# OSSIEPSNew.net
KiCad netlist of a schematic drawn in EAGLE
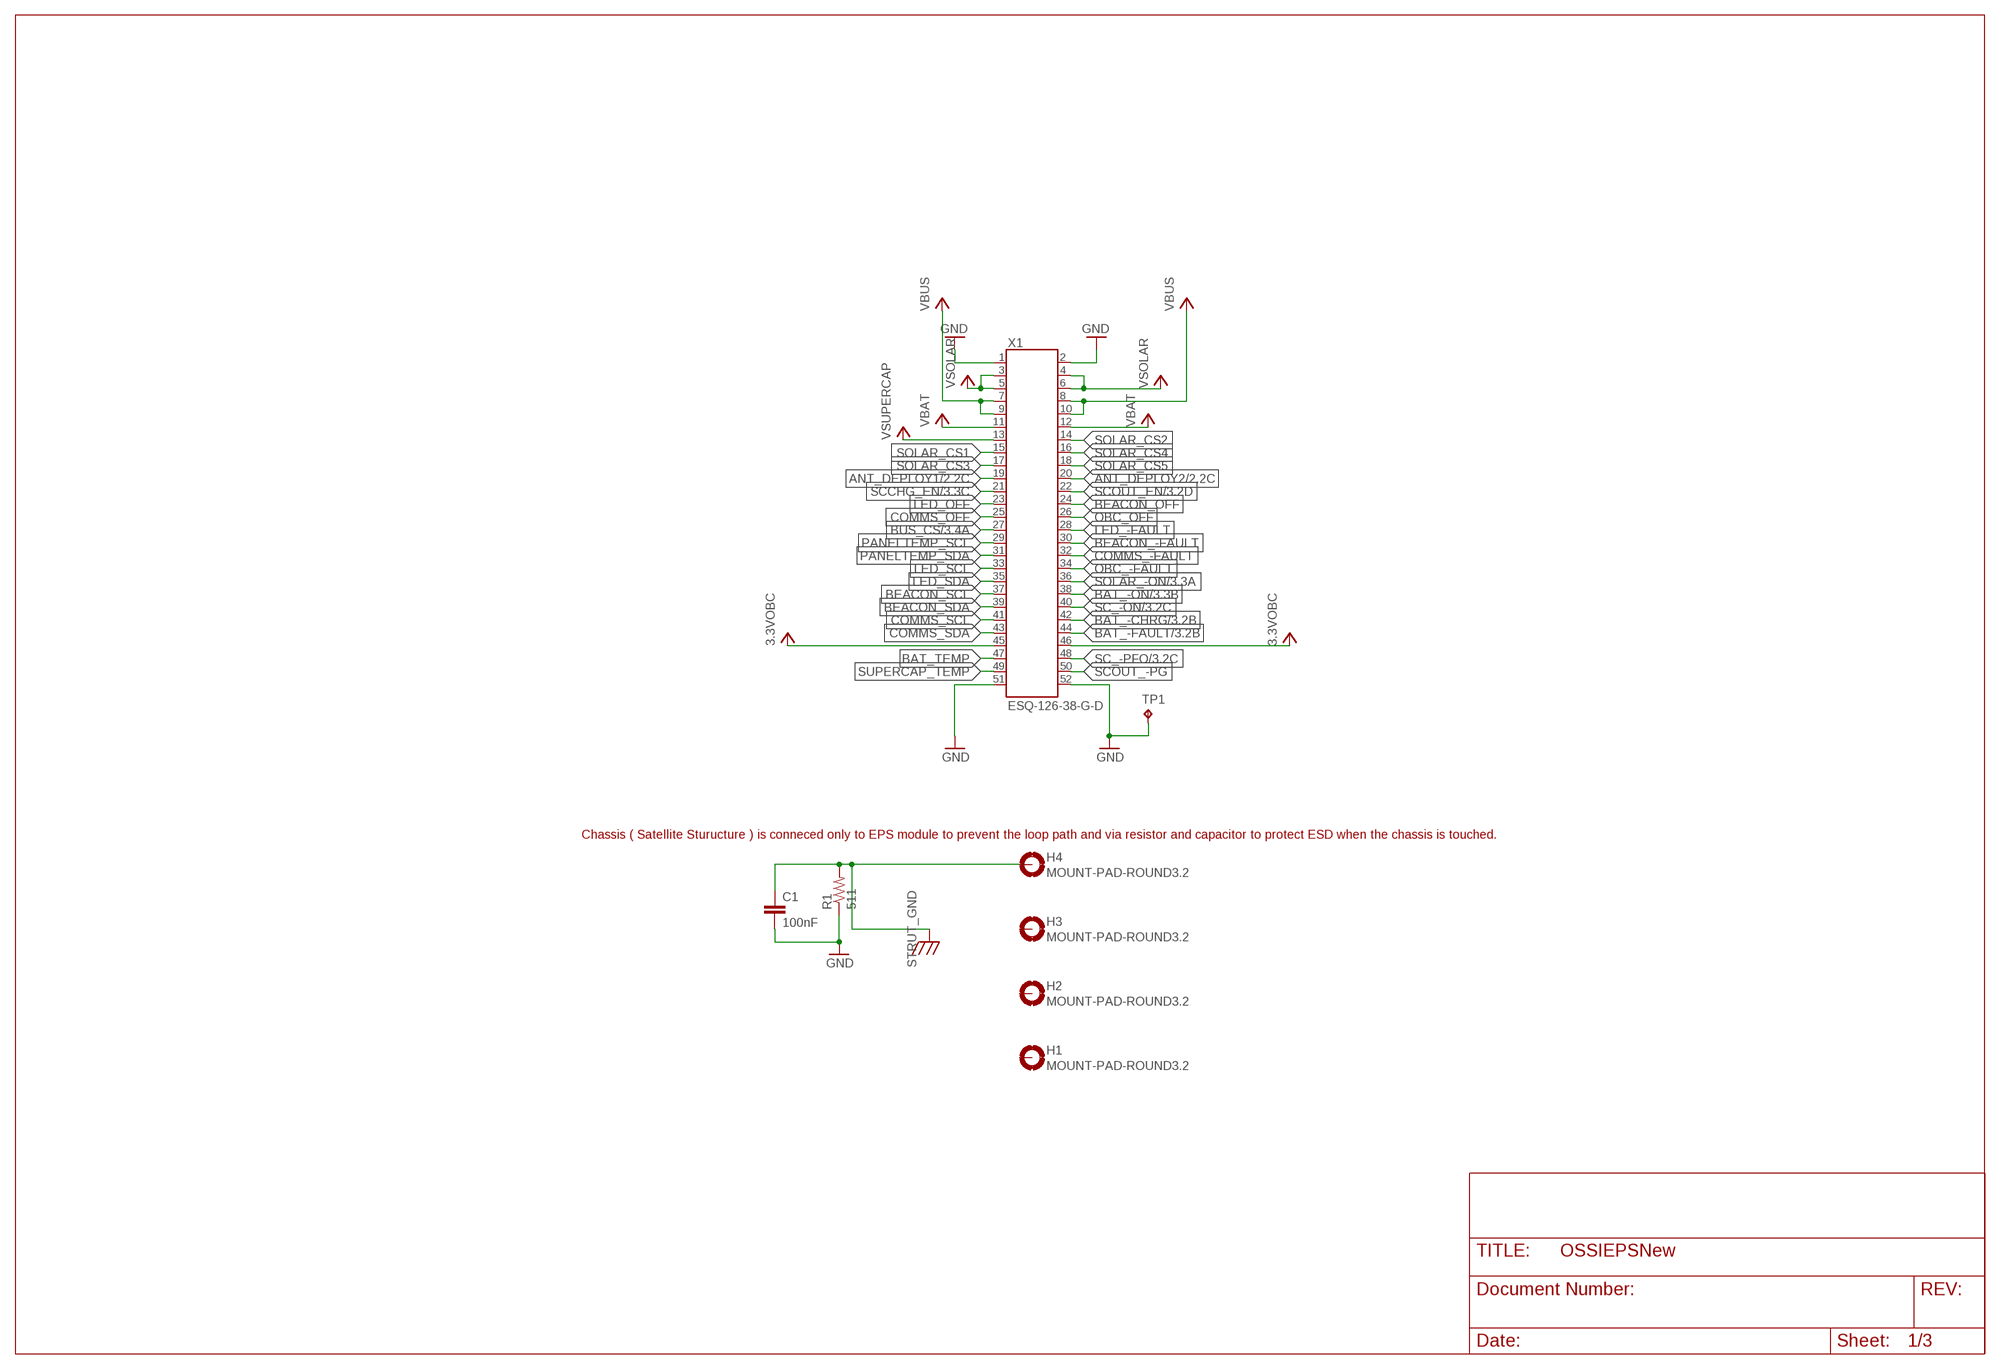
[diagram p0: schematic, sheet 1]
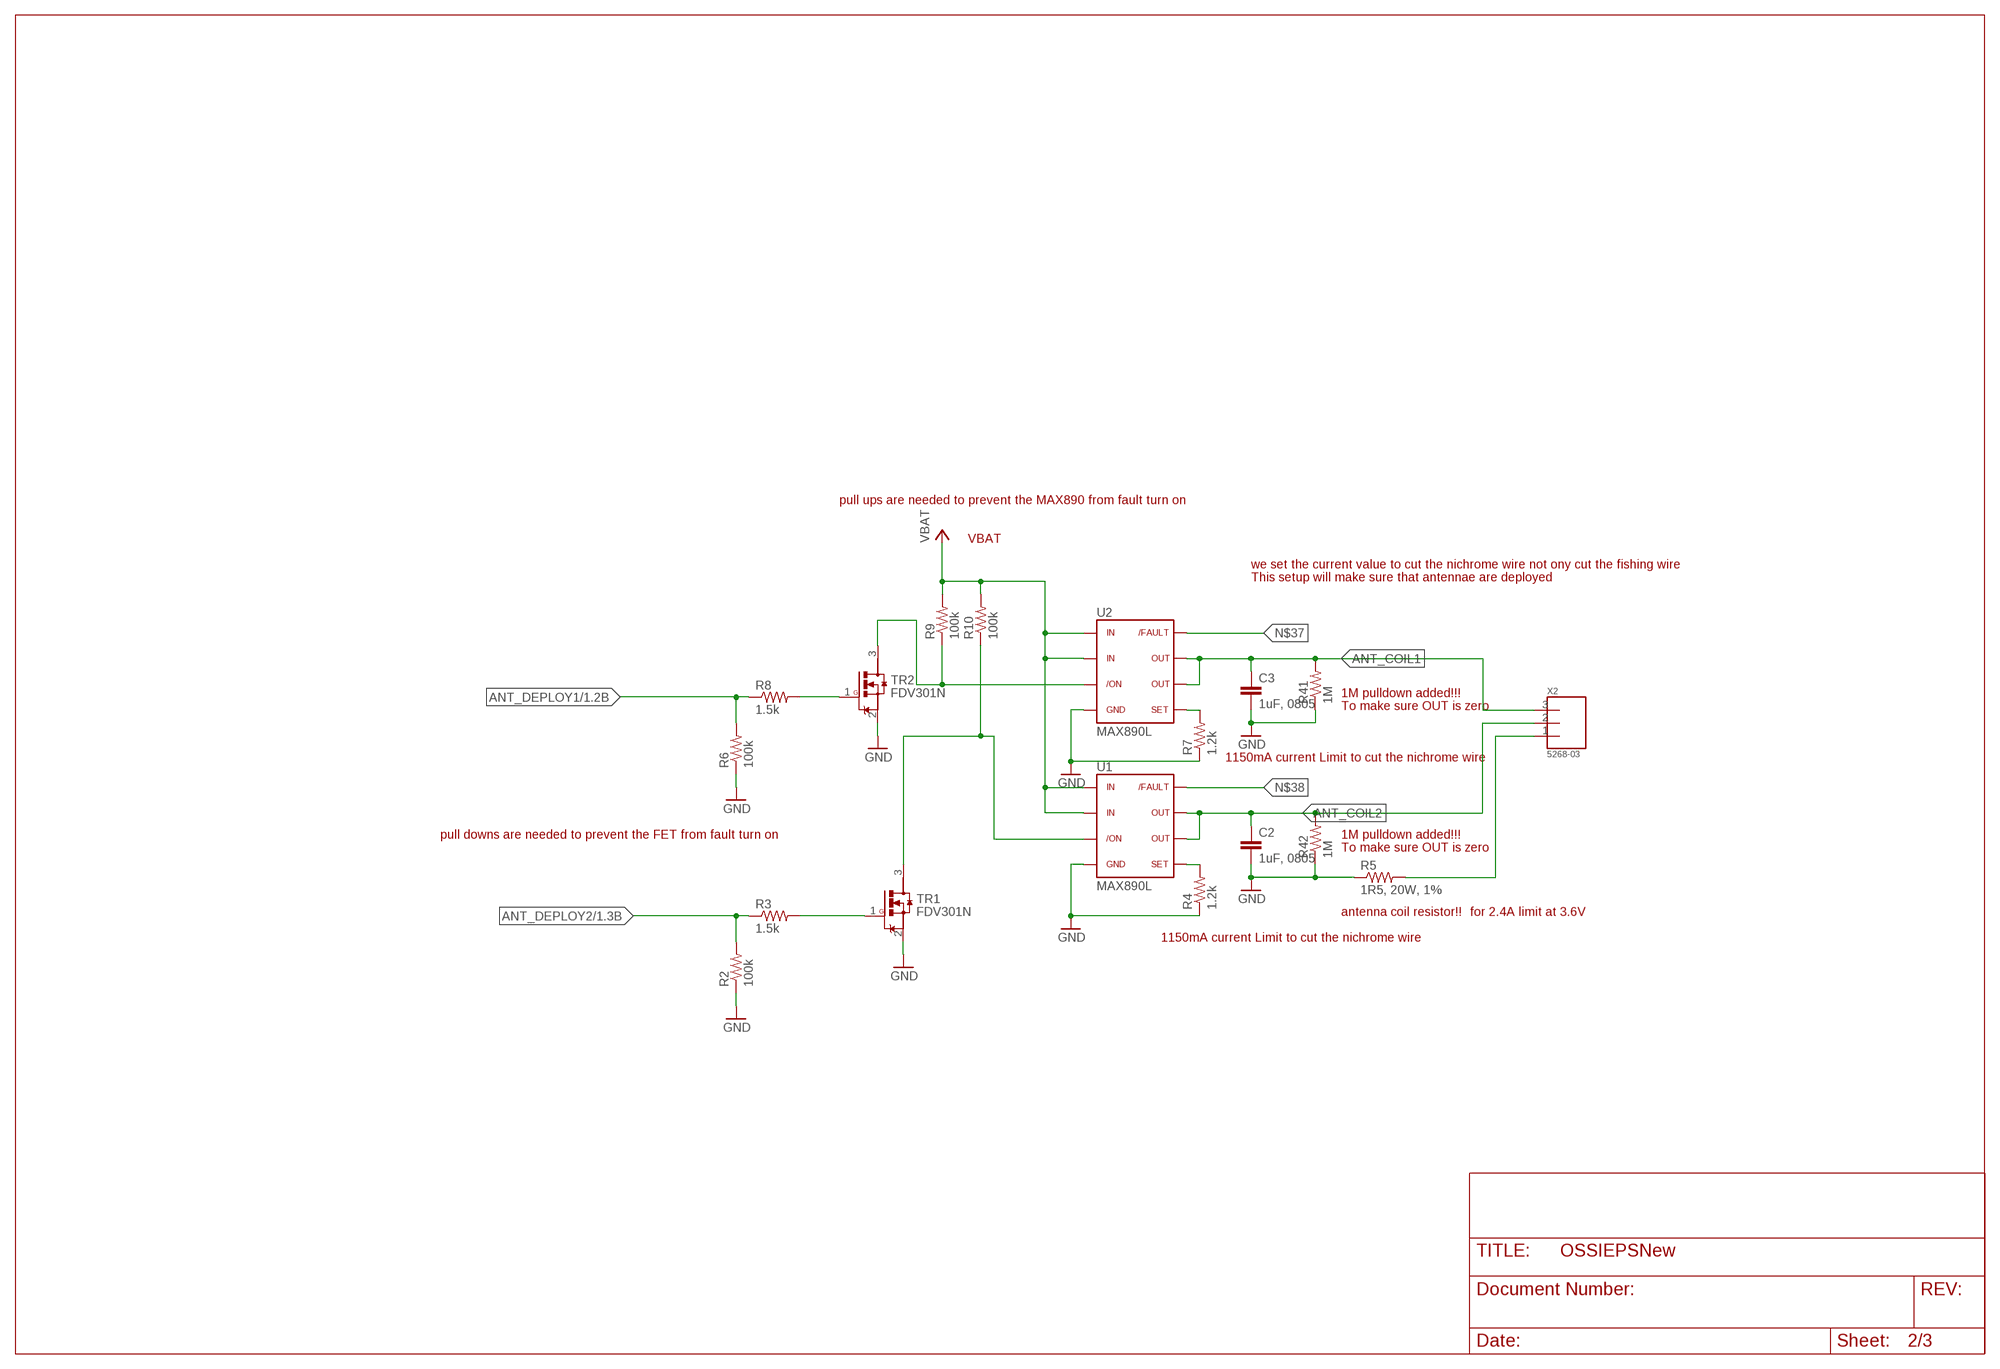
[diagram p1: schematic, sheet 2]
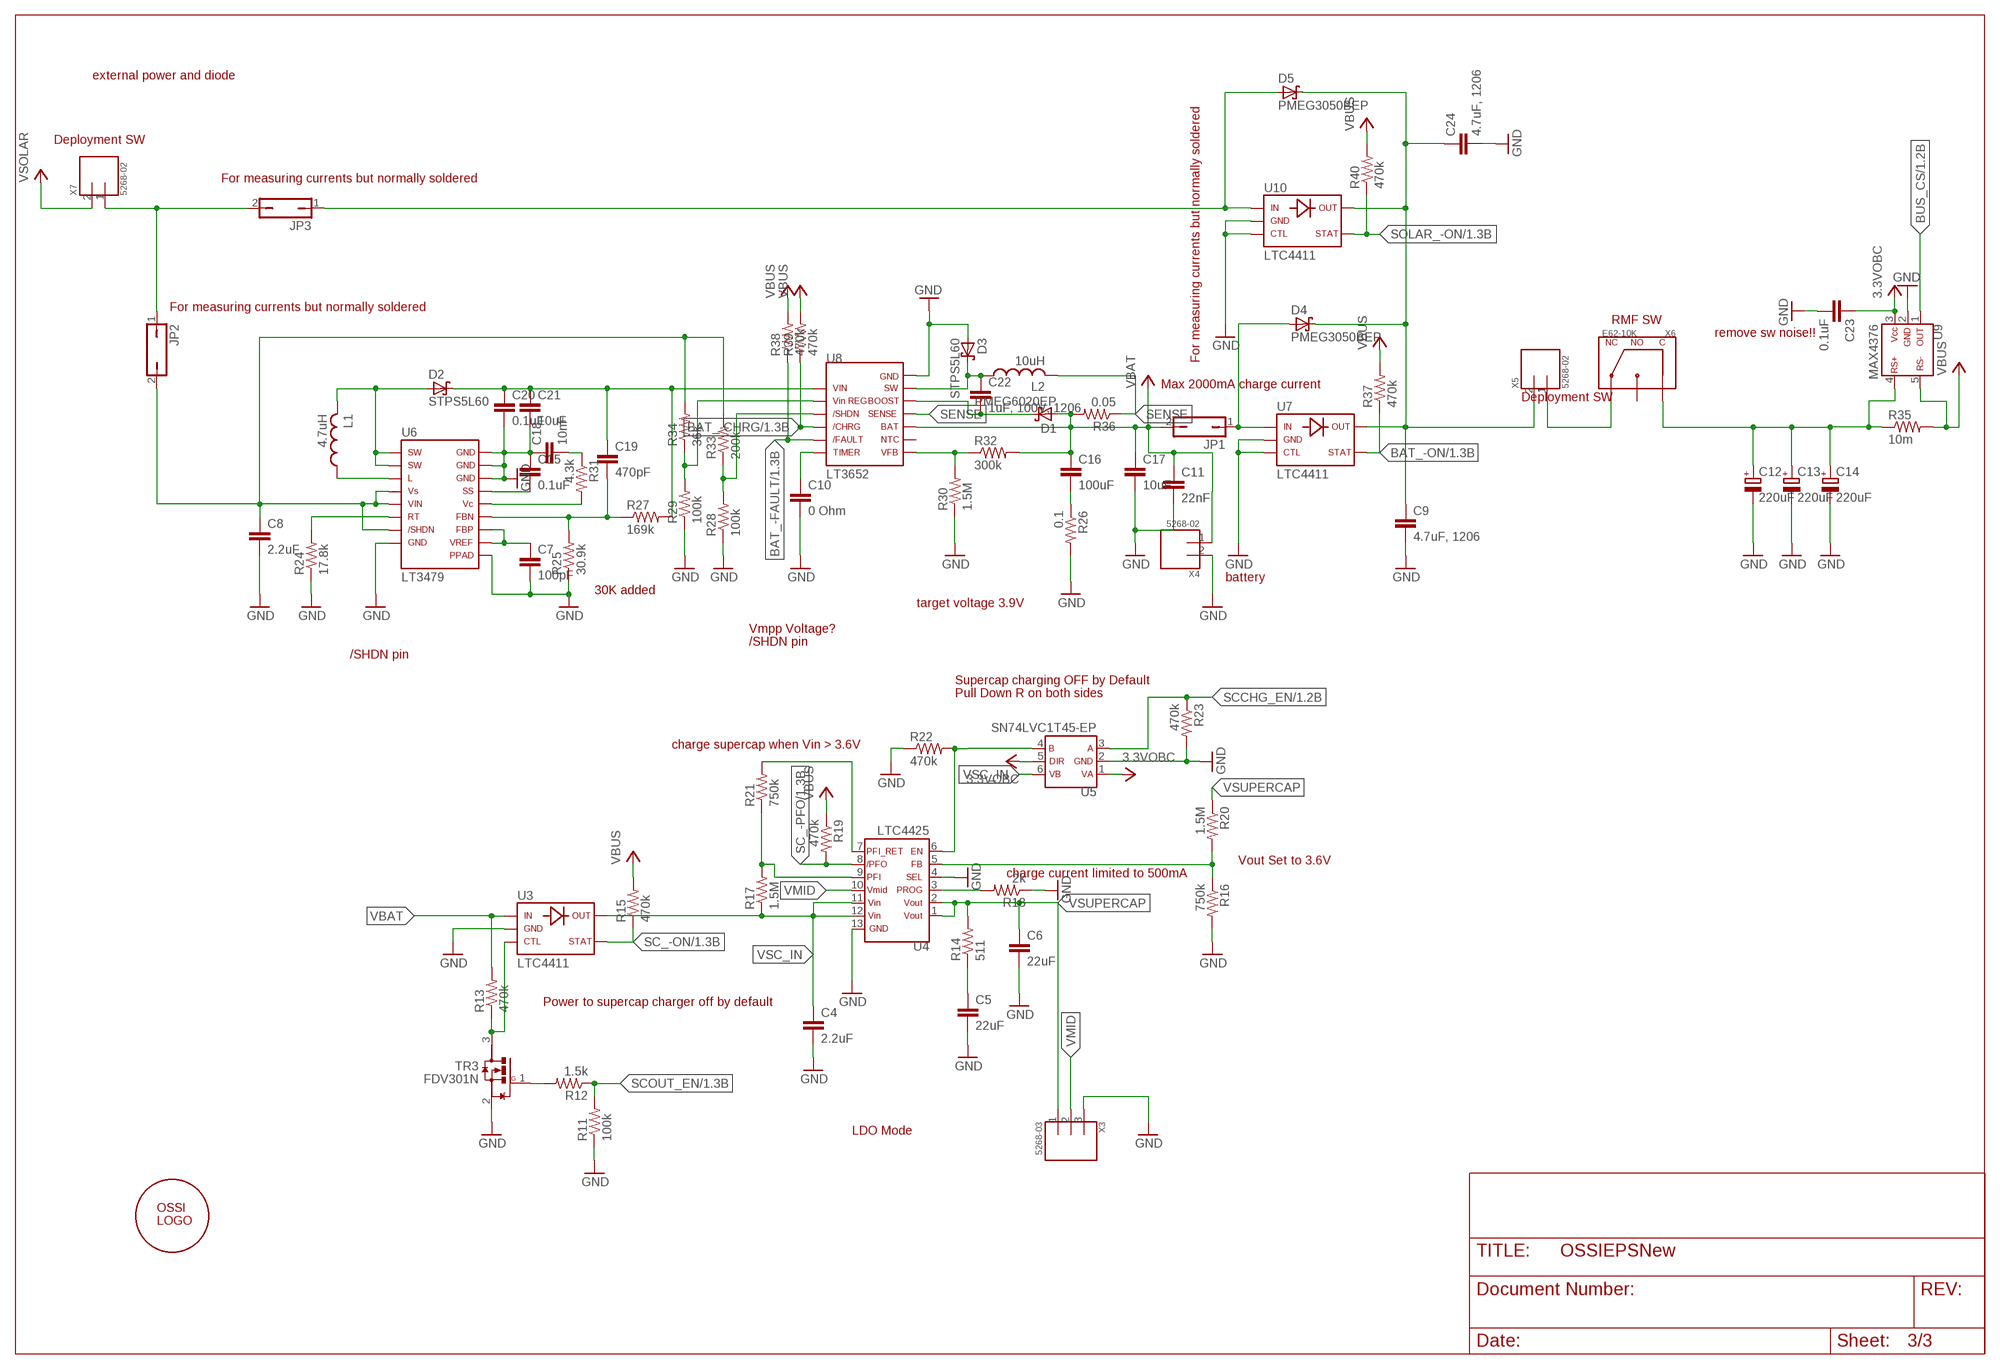
[diagram p2: schematic, sheet 3]

(export (version "E")
  (design (tool "Eeschema 10.0.6"))
  (components
    (comp (ref "C2")
      (value "1uF, 0805")
      (footprint "eagle-import:C0805(2012)")
      (libsource (lib "eagle-import") (part "C0805(2012)"))
    )
    (comp (ref "C3")
      (value "1uF, 0805")
      (footprint "eagle-import:C0805(2012)")
      (libsource (lib "eagle-import") (part "C0805(2012)"))
    )
    (comp (ref "R2")
      (value "100k")
      (footprint "eagle-import:R0603(1608)")
      (libsource (lib "eagle-import") (part "R0603(1608)"))
    )
    (comp (ref "R3")
      (value "1.5k")
      (footprint "eagle-import:R0603(1608)")
      (libsource (lib "eagle-import") (part "R0603(1608)"))
    )
    (comp (ref "R4")
      (value "1.2k")
      (footprint "eagle-import:R0603(1608)")
      (libsource (lib "eagle-import") (part "R0603(1608)"))
    )
    (comp (ref "R5")
      (value "1R5, 20W, 1%")
      (footprint "eagle-import:PWR263S-20")
      (libsource (lib "eagle-import") (part "RPWR263S"))
    )
    (comp (ref "R6")
      (value "100k")
      (footprint "eagle-import:R0603(1608)")
      (libsource (lib "eagle-import") (part "R0603(1608)"))
    )
    (comp (ref "R7")
      (value "1.2k")
      (footprint "eagle-import:R0603(1608)")
      (libsource (lib "eagle-import") (part "R0603(1608)"))
    )
    (comp (ref "R8")
      (value "1.5k")
      (footprint "eagle-import:R0603(1608)")
      (libsource (lib "eagle-import") (part "R0603(1608)"))
    )
    (comp (ref "R9")
      (value "100k")
      (footprint "eagle-import:R0603(1608)")
      (libsource (lib "eagle-import") (part "R0603(1608)"))
    )
    (comp (ref "R10")
      (value "100k")
      (footprint "eagle-import:R0603(1608)")
      (libsource (lib "eagle-import") (part "R0603(1608)"))
    )
    (comp (ref "R41")
      (value "1M")
      (footprint "eagle-import:R0603(1608)")
      (libsource (lib "eagle-import") (part "R0603(1608)"))
    )
    (comp (ref "R42")
      (value "1M")
      (footprint "eagle-import:R0603(1608)")
      (libsource (lib "eagle-import") (part "R0603(1608)"))
    )
    (comp (ref "TR1")
      (value "FDV301N")
      (footprint "eagle-import:SOT23")
      (libsource (lib "eagle-import") (part "FDV301N"))
    )
    (comp (ref "TR2")
      (value "FDV301N")
      (footprint "eagle-import:SOT23")
      (libsource (lib "eagle-import") (part "FDV301N"))
    )
    (comp (ref "U1")
      (value "MAX890L")
      (footprint "eagle-import:SO8")
      (libsource (lib "eagle-import") (part "MAX890L"))
    )
    (comp (ref "U2")
      (value "MAX890L")
      (footprint "eagle-import:SO8")
      (libsource (lib "eagle-import") (part "MAX890L"))
    )
    (comp (ref "X2")
      (value "5268-03")
      (footprint "eagle-import:5268-03")
      (libsource (lib "eagle-import") (part "5268-03"))
    )
    (comp (ref "C1")
      (value "100nF")
      (footprint "eagle-import:C0805(2012)")
      (libsource (lib "eagle-import") (part "C0805(2012)"))
    )
    (comp (ref "H1")
      (value "MOUNT-PAD-ROUND3.2")
      (footprint "eagle-import:3.2-PAD-ROUND")
      (libsource (lib "eagle-import") (part "MOUNT-PAD-ROUND3.2"))
    )
    (comp (ref "H2")
      (value "MOUNT-PAD-ROUND3.2")
      (footprint "eagle-import:3.2-PAD-ROUND")
      (libsource (lib "eagle-import") (part "MOUNT-PAD-ROUND3.2"))
    )
    (comp (ref "H3")
      (value "MOUNT-PAD-ROUND3.2")
      (footprint "eagle-import:3.2-PAD-ROUND")
      (libsource (lib "eagle-import") (part "MOUNT-PAD-ROUND3.2"))
    )
    (comp (ref "H4")
      (value "MOUNT-PAD-ROUND3.2")
      (footprint "eagle-import:3.2-PAD-ROUND")
      (libsource (lib "eagle-import") (part "MOUNT-PAD-ROUND3.2"))
    )
    (comp (ref "R1")
      (value "511")
      (footprint "eagle-import:WSL1206")
      (libsource (lib "eagle-import") (part "RWSL1206"))
    )
    (comp (ref "TP1")
      (value "TP")
      (footprint "eagle-import:TP-13")
      (libsource (lib "eagle-import") (part "TP"))
    )
    (comp (ref "X1")
      (value "ESQ-126-38-G-D")
      (footprint "eagle-import:ESQ-126-XX-X-D")
      (libsource (lib "eagle-import") (part "ESQ-126-38-G-D"))
    )
    (comp (ref "C4")
      (value "2.2uF")
      (footprint "eagle-import:C1206-GCM31")
      (libsource (lib "eagle-import") (part "C1206(3216)-GCM31"))
    )
    (comp (ref "C5")
      (value "22uF")
      (footprint "eagle-import:C1210-GCM32")
      (libsource (lib "eagle-import") (part "C1210(3225)-GCM32"))
    )
    (comp (ref "C6")
      (value "22uF")
      (footprint "eagle-import:C1210-GCM32")
      (libsource (lib "eagle-import") (part "C1210(3225)-GCM32"))
    )
    (comp (ref "C7")
      (value "100pF")
      (footprint "eagle-import:C0603(1608)")
      (libsource (lib "eagle-import") (part "C0603(1608)"))
    )
    (comp (ref "C8")
      (value "2.2uF")
      (footprint "eagle-import:C1206-GCM31")
      (libsource (lib "eagle-import") (part "C1206(3216)-GCM31"))
    )
    (comp (ref "C9")
      (value "4.7uF, 1206")
      (footprint "eagle-import:C1206-GCM31")
      (libsource (lib "eagle-import") (part "C1206(3216)-GCM31"))
    )
    (comp (ref "C10")
      (value "0 Ohm")
      (footprint "eagle-import:C0603(1608)")
      (libsource (lib "eagle-import") (part "C0603(1608)"))
    )
    (comp (ref "C11")
      (value "22nF")
      (footprint "eagle-import:C0603(1608)")
      (libsource (lib "eagle-import") (part "C0603(1608)"))
    )
    (comp (ref "C12")
      (value "220uF")
      (footprint "eagle-import:C2917(7343)-Y")
      (libsource (lib "eagle-import") (part "C-TANTAL-Y"))
    )
    (comp (ref "C13")
      (value "220uF")
      (footprint "eagle-import:C2917(7343)-Y")
      (libsource (lib "eagle-import") (part "C-TANTAL-Y"))
    )
    (comp (ref "C14")
      (value "220uF")
      (footprint "eagle-import:C2917(7343)-Y")
      (libsource (lib "eagle-import") (part "C-TANTAL-Y"))
    )
    (comp (ref "C15")
      (value "0.1uF")
      (footprint "eagle-import:C0603(1608)")
      (libsource (lib "eagle-import") (part "C0603(1608)"))
    )
    (comp (ref "C16")
      (value "100uF")
      (footprint "eagle-import:C1210-TMK325")
      (libsource (lib "eagle-import") (part "C1210(3225)-TMK325"))
    )
    (comp (ref "C17")
      (value "10uF")
      (footprint "eagle-import:C1210-GCM32")
      (libsource (lib "eagle-import") (part "C1210(3225)-GCM32"))
    )
    (comp (ref "C18")
      (value "10nF")
      (footprint "eagle-import:C0603(1608)")
      (libsource (lib "eagle-import") (part "C0603(1608)"))
    )
    (comp (ref "C19")
      (value "470pF")
      (footprint "eagle-import:C0603(1608)")
      (libsource (lib "eagle-import") (part "C0603(1608)"))
    )
    (comp (ref "C20")
      (value "0.1uF")
      (footprint "eagle-import:C0603(1608)")
      (libsource (lib "eagle-import") (part "C0603(1608)"))
    )
    (comp (ref "C21")
      (value "10uF")
      (footprint "eagle-import:C1210-GCM32")
      (libsource (lib "eagle-import") (part "C1210(3225)-GCM32"))
    )
    (comp (ref "C22")
      (value "1uF, 100V, 1206")
      (footprint "eagle-import:C0805(2012)")
      (libsource (lib "eagle-import") (part "C0805(2012)"))
    )
    (comp (ref "C23")
      (value "0.1uF")
      (footprint "eagle-import:C0603(1608)")
      (libsource (lib "eagle-import") (part "C0603(1608)"))
    )
    (comp (ref "C24")
      (value "4.7uF, 1206")
      (footprint "eagle-import:C1206-GCM31")
      (libsource (lib "eagle-import") (part "C1206(3216)-GCM31"))
    )
    (comp (ref "D1")
      (value "PMEG6020EP")
      (footprint "eagle-import:PMEG6020EP")
      (libsource (lib "eagle-import") (part "PMEG6020EP"))
    )
    (comp (ref "D2")
      (value "STPS5L60")
      (footprint "eagle-import:STPS5L60")
      (libsource (lib "eagle-import") (part "STPS5L60"))
    )
    (comp (ref "D3")
      (value "STPS5L60")
      (footprint "eagle-import:STPS5L60")
      (libsource (lib "eagle-import") (part "STPS5L60"))
    )
    (comp (ref "D4")
      (value "PMEG3050BEP")
      (footprint "eagle-import:PMEG6020EP")
      (libsource (lib "eagle-import") (part "PMEG6020EP"))
    )
    (comp (ref "D5")
      (value "PMEG3050BEP")
      (footprint "eagle-import:PMEG6020EP")
      (libsource (lib "eagle-import") (part "PMEG6020EP"))
    )
    (comp (ref "JP1")
      (value "JP1Q")
      (footprint "eagle-import:JP1")
      (libsource (lib "eagle-import") (part "JP1Q"))
    )
    (comp (ref "JP2")
      (value "JP1Q")
      (footprint "eagle-import:JP1")
      (libsource (lib "eagle-import") (part "JP1Q"))
    )
    (comp (ref "JP3")
      (value "JP1Q")
      (footprint "eagle-import:JP1")
      (libsource (lib "eagle-import") (part "JP1Q"))
    )
    (comp (ref "L1")
      (value "4.7uH")
      (footprint "eagle-import:RLF7030")
      (libsource (lib "eagle-import") (part "LRLF7030"))
    )
    (comp (ref "L2")
      (value "10uH")
      (footprint "eagle-import:RLF12545")
      (libsource (lib "eagle-import") (part "LRLF12545"))
    )
    (comp (ref "R11")
      (value "100k")
      (footprint "eagle-import:R0603(1608)")
      (libsource (lib "eagle-import") (part "R0603(1608)"))
    )
    (comp (ref "R12")
      (value "1.5k")
      (footprint "eagle-import:R0603(1608)")
      (libsource (lib "eagle-import") (part "R0603(1608)"))
    )
    (comp (ref "R13")
      (value "470k")
      (footprint "eagle-import:R0603(1608)")
      (libsource (lib "eagle-import") (part "R0603(1608)"))
    )
    (comp (ref "R14")
      (value "511")
      (footprint "eagle-import:WSL1206")
      (libsource (lib "eagle-import") (part "RWSL1206"))
    )
    (comp (ref "R15")
      (value "470k")
      (footprint "eagle-import:R0603(1608)")
      (libsource (lib "eagle-import") (part "R0603(1608)"))
    )
    (comp (ref "R16")
      (value "750k")
      (footprint "eagle-import:R0603(1608)")
      (libsource (lib "eagle-import") (part "R0603(1608)"))
    )
    (comp (ref "R17")
      (value "1.5M")
      (footprint "eagle-import:R0603(1608)")
      (libsource (lib "eagle-import") (part "R0603(1608)"))
    )
    (comp (ref "R18")
      (value "2k")
      (footprint "eagle-import:R0603(1608)")
      (libsource (lib "eagle-import") (part "R0603(1608)"))
    )
    (comp (ref "R19")
      (value "470k")
      (footprint "eagle-import:R0603(1608)")
      (libsource (lib "eagle-import") (part "R0603(1608)"))
    )
    (comp (ref "R20")
      (value "1.5M")
      (footprint "eagle-import:R0603(1608)")
      (libsource (lib "eagle-import") (part "R0603(1608)"))
    )
    (comp (ref "R21")
      (value "750k")
      (footprint "eagle-import:R0603(1608)")
      (libsource (lib "eagle-import") (part "R0603(1608)"))
    )
    (comp (ref "R22")
      (value "470k")
      (footprint "eagle-import:R0603(1608)")
      (libsource (lib "eagle-import") (part "R0603(1608)"))
    )
    (comp (ref "R23")
      (value "470k")
      (footprint "eagle-import:R0603(1608)")
      (libsource (lib "eagle-import") (part "R0603(1608)"))
    )
    (comp (ref "R24")
      (value "17.8k")
      (footprint "eagle-import:R0603(1608)")
      (libsource (lib "eagle-import") (part "R0603(1608)"))
    )
    (comp (ref "R25")
      (value "30.9k")
      (footprint "eagle-import:R0603(1608)")
      (libsource (lib "eagle-import") (part "R0603(1608)"))
    )
    (comp (ref "R26")
      (value "0.1")
      (footprint "eagle-import:WSL1206")
      (libsource (lib "eagle-import") (part "RWSL1206"))
    )
    (comp (ref "R27")
      (value "169k")
      (footprint "eagle-import:R0603(1608)")
      (libsource (lib "eagle-import") (part "R0603(1608)"))
    )
    (comp (ref "R28")
      (value "100k")
      (footprint "eagle-import:R0603(1608)")
      (libsource (lib "eagle-import") (part "R0603(1608)"))
    )
    (comp (ref "R29")
      (value "100k")
      (footprint "eagle-import:R0603(1608)")
      (libsource (lib "eagle-import") (part "R0603(1608)"))
    )
    (comp (ref "R30")
      (value "1.5M")
      (footprint "eagle-import:R0603(1608)")
      (libsource (lib "eagle-import") (part "R0603(1608)"))
    )
    (comp (ref "R31")
      (value "4.3k")
      (footprint "eagle-import:R0603(1608)")
      (libsource (lib "eagle-import") (part "R0603(1608)"))
    )
    (comp (ref "R32")
      (value "300k")
      (footprint "eagle-import:R0603(1608)")
      (libsource (lib "eagle-import") (part "R0603(1608)"))
    )
    (comp (ref "R33")
      (value "200k")
      (footprint "eagle-import:R0603(1608)")
      (libsource (lib "eagle-import") (part "R0603(1608)"))
    )
    (comp (ref "R34")
      (value "36k")
      (footprint "eagle-import:R0603(1608)")
      (libsource (lib "eagle-import") (part "R0603(1608)"))
    )
    (comp (ref "R35")
      (value "10m")
      (footprint "eagle-import:WSL1206")
      (libsource (lib "eagle-import") (part "RWSL1206"))
    )
    (comp (ref "R36")
      (value "0.05")
      (footprint "eagle-import:WSL1206")
      (libsource (lib "eagle-import") (part "RWSL1206"))
    )
    (comp (ref "R37")
      (value "470k")
      (footprint "eagle-import:R0603(1608)")
      (libsource (lib "eagle-import") (part "R0603(1608)"))
    )
    (comp (ref "R38")
      (value "470k")
      (footprint "eagle-import:R0603(1608)")
      (libsource (lib "eagle-import") (part "R0603(1608)"))
    )
    (comp (ref "R39")
      (value "470k")
      (footprint "eagle-import:R0603(1608)")
      (libsource (lib "eagle-import") (part "R0603(1608)"))
    )
    (comp (ref "R40")
      (value "470k")
      (footprint "eagle-import:R0603(1608)")
      (libsource (lib "eagle-import") (part "R0603(1608)"))
    )
    (comp (ref "TR3")
      (value "FDV301N")
      (footprint "eagle-import:SOT23")
      (libsource (lib "eagle-import") (part "FDV301N"))
    )
    (comp (ref "U$1")
      (value "OSSILOGORECT")
      (footprint "eagle-import:OSSILOGORECT1005")
      (libsource (lib "eagle-import") (part "OSSILOGORECT"))
    )
    (comp (ref "U3")
      (value "LTC4411")
      (footprint "eagle-import:TSOT23-5")
      (libsource (lib "eagle-import") (part "LTC4411"))
    )
    (comp (ref "U4")
      (value "LTC4425")
      (footprint "eagle-import:MSE")
      (libsource (lib "eagle-import") (part "LTC4425"))
    )
    (comp (ref "U5")
      (value "SN74LVC1T45-EP")
      (footprint "eagle-import:SOT-6DCK")
      (libsource (lib "eagle-import") (part "SN74LVC1T45-EP"))
    )
    (comp (ref "U6")
      (value "LT3479")
      (footprint "eagle-import:TSSOP16-FE")
      (libsource (lib "eagle-import") (part "LT3479"))
    )
    (comp (ref "U7")
      (value "LTC4411")
      (footprint "eagle-import:TSOT23-5")
      (libsource (lib "eagle-import") (part "LTC4411"))
    )
    (comp (ref "U8")
      (value "LT3652")
      (footprint "eagle-import:MSE")
      (libsource (lib "eagle-import") (part "LT3652"))
    )
    (comp (ref "U9")
      (value "MAX4376")
      (footprint "eagle-import:SOT23-5DBV")
      (libsource (lib "eagle-import") (part "MAX4376"))
    )
    (comp (ref "U10")
      (value "LTC4411")
      (footprint "eagle-import:TSOT23-5")
      (libsource (lib "eagle-import") (part "LTC4411"))
    )
    (comp (ref "X3")
      (value "5268-03")
      (footprint "eagle-import:5268-03")
      (libsource (lib "eagle-import") (part "5268-03"))
    )
    (comp (ref "X4")
      (value "5268-02")
      (footprint "eagle-import:5628-02")
      (libsource (lib "eagle-import") (part "5268-02"))
    )
    (comp (ref "X5")
      (value "5268-02")
      (footprint "eagle-import:5628-02")
      (libsource (lib "eagle-import") (part "5268-02"))
    )
    (comp (ref "X6")
      (value "E62-10K")
      (footprint "eagle-import:E62-10K")
      (libsource (lib "eagle-import") (part "E62-10K"))
    )
    (comp (ref "X7")
      (value "5268-02")
      (footprint "eagle-import:5628-02")
      (libsource (lib "eagle-import") (part "5268-02"))
    )
  )
  (nets
    (net (code "1") (name "3.3VOBC") (class "Default")
      (node (ref "C23") (pin "1") (pinfunction "1_1") (pintype "passive"))
      (node (ref "U5") (pin "1") (pinfunction "P$1_1") (pintype "bidirectional"))
      (node (ref "U5") (pin "5") (pinfunction "P$5_5") (pintype "bidirectional"))
      (node (ref "U9") (pin "3") (pinfunction "P$3_3") (pintype "power_in"))
      (node (ref "X1") (pin "45") (pinfunction "45_45") (pintype "bidirectional"))
      (node (ref "X1") (pin "46") (pinfunction "46_46") (pintype "bidirectional"))
    )
    (net (code "2") (name "ANT_COIL1") (class "Default")
      (node (ref "C3") (pin "1") (pinfunction "1_1") (pintype "passive"))
      (node (ref "R41") (pin "2") (pinfunction "2_2") (pintype "passive"))
      (node (ref "U2") (pin "6") (pinfunction "P$6_6") (pintype "output"))
      (node (ref "U2") (pin "7") (pinfunction "P$7_7") (pintype "output"))
      (node (ref "X2") (pin "3") (pinfunction "3_3") (pintype "bidirectional"))
    )
    (net (code "3") (name "ANT_COIL2") (class "Default")
      (node (ref "C2") (pin "1") (pinfunction "1_1") (pintype "passive"))
      (node (ref "R42") (pin "2") (pinfunction "2_2") (pintype "passive"))
      (node (ref "U1") (pin "6") (pinfunction "P$6_6") (pintype "output"))
      (node (ref "U1") (pin "7") (pinfunction "P$7_7") (pintype "output"))
      (node (ref "X2") (pin "2") (pinfunction "2_2") (pintype "bidirectional"))
    )
    (net (code "4") (name "ANT_DEPLOY1") (class "Default")
      (node (ref "R6") (pin "2") (pinfunction "2_2") (pintype "passive"))
      (node (ref "R8") (pin "1") (pinfunction "1_1") (pintype "passive"))
      (node (ref "X1") (pin "19") (pinfunction "19_19") (pintype "bidirectional"))
    )
    (net (code "5") (name "ANT_DEPLOY2") (class "Default")
      (node (ref "R2") (pin "2") (pinfunction "2_2") (pintype "passive"))
      (node (ref "R3") (pin "1") (pinfunction "1_1") (pintype "passive"))
      (node (ref "X1") (pin "20") (pinfunction "20_20") (pintype "bidirectional"))
    )
    (net (code "6") (name "BAT_-CHRG") (class "Default")
      (node (ref "R39") (pin "1") (pinfunction "1_1") (pintype "passive"))
      (node (ref "U8") (pin "4") (pinfunction "P$4_4") (pintype "output"))
      (node (ref "X1") (pin "42") (pinfunction "42_42") (pintype "bidirectional"))
    )
    (net (code "7") (name "BAT_-FAULT") (class "Default")
      (node (ref "R38") (pin "1") (pinfunction "1_1") (pintype "passive"))
      (node (ref "U8") (pin "5") (pinfunction "P$5_5") (pintype "output"))
      (node (ref "X1") (pin "44") (pinfunction "44_44") (pintype "bidirectional"))
    )
    (net (code "8") (name "BAT_-ON") (class "Default")
      (node (ref "R37") (pin "1") (pinfunction "1_1") (pintype "passive"))
      (node (ref "U7") (pin "P$4") (pinfunction "P$4_P$4") (pintype "output"))
      (node (ref "X1") (pin "38") (pinfunction "38_38") (pintype "bidirectional"))
    )
    (net (code "9") (name "BAT_TEMP") (class "Default")
      (node (ref "X1") (pin "47") (pinfunction "47_47") (pintype "bidirectional"))
    )
    (net (code "10") (name "BEACON_-FAULT") (class "Default")
      (node (ref "X1") (pin "30") (pinfunction "30_30") (pintype "bidirectional"))
    )
    (net (code "11") (name "BEACON_OFF") (class "Default")
      (node (ref "X1") (pin "24") (pinfunction "24_24") (pintype "bidirectional"))
    )
    (net (code "12") (name "BEACON_SCL") (class "Default")
      (node (ref "X1") (pin "37") (pinfunction "37_37") (pintype "bidirectional"))
    )
    (net (code "13") (name "BEACON_SDA") (class "Default")
      (node (ref "X1") (pin "39") (pinfunction "39_39") (pintype "bidirectional"))
    )
    (net (code "14") (name "BUS_CS") (class "Default")
      (node (ref "U9") (pin "1") (pinfunction "P$1_1") (pintype "output"))
      (node (ref "X1") (pin "27") (pinfunction "27_27") (pintype "bidirectional"))
    )
    (net (code "15") (name "COMMS_-FAULT") (class "Default")
      (node (ref "X1") (pin "32") (pinfunction "32_32") (pintype "bidirectional"))
    )
    (net (code "16") (name "COMMS_OFF") (class "Default")
      (node (ref "X1") (pin "25") (pinfunction "25_25") (pintype "bidirectional"))
    )
    (net (code "17") (name "COMMS_SCL") (class "Default")
      (node (ref "X1") (pin "41") (pinfunction "41_41") (pintype "bidirectional"))
    )
    (net (code "18") (name "COMMS_SDA") (class "Default")
      (node (ref "X1") (pin "43") (pinfunction "43_43") (pintype "bidirectional"))
    )
    (net (code "19") (name "GND") (class "Default")
      (node (ref "C1") (pin "2") (pinfunction "2_2") (pintype "passive"))
      (node (ref "C10") (pin "2") (pinfunction "2_2") (pintype "passive"))
      (node (ref "C11") (pin "2") (pinfunction "2_2") (pintype "passive"))
      (node (ref "C12") (pin "2") (pinfunction "-_2") (pintype "passive"))
      (node (ref "C13") (pin "2") (pinfunction "-_2") (pintype "passive"))
      (node (ref "C14") (pin "2") (pinfunction "-_2") (pintype "passive"))
      (node (ref "C15") (pin "1") (pinfunction "1_1") (pintype "passive"))
      (node (ref "C17") (pin "P$2") (pinfunction "2_P$2") (pintype "passive"))
      (node (ref "C18") (pin "1") (pinfunction "1_1") (pintype "passive"))
      (node (ref "C2") (pin "2") (pinfunction "2_2") (pintype "passive"))
      (node (ref "C20") (pin "2") (pinfunction "2_2") (pintype "passive"))
      (node (ref "C21") (pin "P$2") (pinfunction "2_P$2") (pintype "passive"))
      (node (ref "C23") (pin "2") (pinfunction "2_2") (pintype "passive"))
      (node (ref "C24") (pin "P$2") (pinfunction "2_P$2") (pintype "passive"))
      (node (ref "C3") (pin "2") (pinfunction "2_2") (pintype "passive"))
      (node (ref "C4") (pin "P$2") (pinfunction "2_P$2") (pintype "passive"))
      (node (ref "C5") (pin "P$2") (pinfunction "2_P$2") (pintype "passive"))
      (node (ref "C6") (pin "P$2") (pinfunction "2_P$2") (pintype "passive"))
      (node (ref "C7") (pin "2") (pinfunction "2_2") (pintype "passive"))
      (node (ref "C8") (pin "P$2") (pinfunction "2_P$2") (pintype "passive"))
      (node (ref "C9") (pin "P$2") (pinfunction "2_P$2") (pintype "passive"))
      (node (ref "D3") (pin "A") (pinfunction "A_A") (pintype "passive"))
      (node (ref "R1") (pin "P$1") (pinfunction "1_P$1") (pintype "passive"))
      (node (ref "R11") (pin "1") (pinfunction "1_1") (pintype "passive"))
      (node (ref "R16") (pin "2") (pinfunction "2_2") (pintype "passive"))
      (node (ref "R18") (pin "1") (pinfunction "1_1") (pintype "passive"))
      (node (ref "R2") (pin "1") (pinfunction "1_1") (pintype "passive"))
      (node (ref "R22") (pin "1") (pinfunction "1_1") (pintype "passive"))
      (node (ref "R23") (pin "2") (pinfunction "2_2") (pintype "passive"))
      (node (ref "R24") (pin "1") (pinfunction "1_1") (pintype "passive"))
      (node (ref "R25") (pin "1") (pinfunction "1_1") (pintype "passive"))
      (node (ref "R26") (pin "P$2") (pinfunction "2_P$2") (pintype "passive"))
      (node (ref "R28") (pin "1") (pinfunction "1_1") (pintype "passive"))
      (node (ref "R29") (pin "1") (pinfunction "1_1") (pintype "passive"))
      (node (ref "R30") (pin "1") (pinfunction "1_1") (pintype "passive"))
      (node (ref "R4") (pin "1") (pinfunction "1_1") (pintype "passive"))
      (node (ref "R41") (pin "1") (pinfunction "1_1") (pintype "passive"))
      (node (ref "R42") (pin "1") (pinfunction "1_1") (pintype "passive"))
      (node (ref "R5") (pin "P$1") (pinfunction "1_P$1") (pintype "passive"))
      (node (ref "R6") (pin "1") (pinfunction "1_1") (pintype "passive"))
      (node (ref "R7") (pin "1") (pinfunction "1_1") (pintype "passive"))
      (node (ref "TP1") (pin "TP") (pinfunction "TP_TP") (pintype "input"))
      (node (ref "TR1") (pin "2") (pinfunction "S_2") (pintype "bidirectional"))
      (node (ref "TR2") (pin "2") (pinfunction "S_2") (pintype "bidirectional"))
      (node (ref "TR3") (pin "2") (pinfunction "S_2") (pintype "bidirectional"))
      (node (ref "U1") (pin "4") (pinfunction "P$4_4") (pintype "power_in"))
      (node (ref "U10") (pin "P$2") (pinfunction "P$2_P$2") (pintype "power_in"))
      (node (ref "U10") (pin "P$3") (pinfunction "P$3_P$3") (pintype "input"))
      (node (ref "U2") (pin "4") (pinfunction "P$4_4") (pintype "power_in"))
      (node (ref "U3") (pin "P$2") (pinfunction "P$2_P$2") (pintype "power_in"))
      (node (ref "U4") (pin "13") (pinfunction "P$13_13") (pintype "power_in"))
      (node (ref "U4") (pin "4") (pinfunction "P$4_4") (pintype "input"))
      (node (ref "U5") (pin "2") (pinfunction "P$2_2") (pintype "bidirectional"))
      (node (ref "U6") (pin "14") (pinfunction "P$14_14") (pintype "power_in"))
      (node (ref "U6") (pin "15") (pinfunction "P$15_15") (pintype "power_in"))
      (node (ref "U6") (pin "16") (pinfunction "P$16_16") (pintype "power_in"))
      (node (ref "U6") (pin "8") (pinfunction "P$8_8") (pintype "power_in"))
      (node (ref "U6") (pin "PPAD") (pinfunction "P$17_PPAD") (pintype "power_in"))
      (node (ref "U7") (pin "P$2") (pinfunction "P$2_P$2") (pintype "power_in"))
      (node (ref "U7") (pin "P$3") (pinfunction "P$3_P$3") (pintype "input"))
      (node (ref "U8") (pin "13") (pinfunction "P$13_13") (pintype "bidirectional"))
      (node (ref "U9") (pin "2") (pinfunction "P$2_2") (pintype "power_in"))
      (node (ref "X1") (pin "1") (pinfunction "1_1") (pintype "bidirectional"))
      (node (ref "X1") (pin "2") (pinfunction "2_2") (pintype "bidirectional"))
      (node (ref "X1") (pin "51") (pinfunction "51_51") (pintype "bidirectional"))
      (node (ref "X1") (pin "52") (pinfunction "52_52") (pintype "bidirectional"))
      (node (ref "X3") (pin "3") (pinfunction "3_3") (pintype "bidirectional"))
      (node (ref "X4") (pin "2") (pinfunction "2_2") (pintype "bidirectional"))
    )
    (net (code "20") (name "LED_-FAULT") (class "Default")
      (node (ref "X1") (pin "28") (pinfunction "28_28") (pintype "bidirectional"))
    )
    (net (code "21") (name "LED_OFF") (class "Default")
      (node (ref "X1") (pin "23") (pinfunction "23_23") (pintype "bidirectional"))
    )
    (net (code "22") (name "LED_SCL") (class "Default")
      (node (ref "X1") (pin "33") (pinfunction "33_33") (pintype "bidirectional"))
    )
    (net (code "23") (name "LED_SDA") (class "Default")
      (node (ref "X1") (pin "35") (pinfunction "35_35") (pintype "bidirectional"))
    )
    (net (code "24") (name "N$37") (class "Default")
      (node (ref "U2") (pin "8") (pinfunction "P$8_8") (pintype "output"))
    )
    (net (code "25") (name "N$38") (class "Default")
      (node (ref "U1") (pin "8") (pinfunction "P$8_8") (pintype "output"))
    )
    (net (code "26") (name "Net-(C5-1)") (class "Default")
      (node (ref "C5") (pin "P$1") (pinfunction "1_P$1") (pintype "passive"))
      (node (ref "R14") (pin "P$1") (pinfunction "1_P$1") (pintype "passive"))
    )
    (net (code "27") (name "Net-(C8-1)") (class "Default")
      (node (ref "C8") (pin "P$1") (pinfunction "1_P$1") (pintype "passive"))
      (node (ref "JP2") (pin "2") (pinfunction "2_2") (pintype "passive"))
      (node (ref "R33") (pin "2") (pinfunction "2_2") (pintype "passive"))
      (node (ref "R34") (pin "2") (pinfunction "2_2") (pintype "passive"))
      (node (ref "U6") (pin "4") (pinfunction "P$4_4") (pintype "power_in"))
      (node (ref "U6") (pin "5") (pinfunction "P$5_5") (pintype "power_in"))
      (node (ref "U6") (pin "7") (pinfunction "P$7_7") (pintype "input"))
    )
    (net (code "28") (name "Net-(C12-+)") (class "Default")
      (node (ref "C12") (pin "1") (pinfunction "+_1") (pintype "passive"))
      (node (ref "C13") (pin "1") (pinfunction "+_1") (pintype "passive"))
      (node (ref "C14") (pin "1") (pinfunction "+_1") (pintype "passive"))
      (node (ref "R35") (pin "P$1") (pinfunction "1_P$1") (pintype "passive"))
      (node (ref "U9") (pin "4") (pinfunction "P$4_4") (pintype "input"))
      (node (ref "X6") (pin "C") (pinfunction "C_C") (pintype "bidirectional"))
    )
    (net (code "29") (name "Net-(C16-2)") (class "Default")
      (node (ref "C16") (pin "P$2") (pinfunction "2_P$2") (pintype "passive"))
      (node (ref "R26") (pin "P$1") (pinfunction "1_P$1") (pintype "passive"))
    )
    (net (code "30") (name "Net-(C18-Pad2)") (class "Default")
      (node (ref "C18") (pin "2") (pinfunction "2_2") (pintype "passive"))
      (node (ref "R31") (pin "1") (pinfunction "1_1") (pintype "passive"))
    )
    (net (code "31") (name "Net-(C21-1)") (class "Default")
      (node (ref "C19") (pin "1") (pinfunction "1_1") (pintype "passive"))
      (node (ref "C20") (pin "1") (pinfunction "1_1") (pintype "passive"))
      (node (ref "C21") (pin "P$1") (pinfunction "1_P$1") (pintype "passive"))
      (node (ref "D2") (pin "C") (pinfunction "C_C") (pintype "passive"))
      (node (ref "R27") (pin "2") (pinfunction "2_2") (pintype "passive"))
      (node (ref "U8") (pin "1") (pinfunction "P$1_1") (pintype "power_in"))
    )
    (net (code "32") (name "Net-(C24-1)") (class "Default")
      (node (ref "C24") (pin "P$1") (pinfunction "1_P$1") (pintype "passive"))
      (node (ref "C9") (pin "P$1") (pinfunction "1_P$1") (pintype "passive"))
      (node (ref "D4") (pin "C") (pinfunction "C_C") (pintype "passive"))
      (node (ref "D5") (pin "C") (pinfunction "C_C") (pintype "passive"))
      (node (ref "U10") (pin "P$5") (pinfunction "P$5_P$5") (pintype "power_in"))
      (node (ref "U7") (pin "P$5") (pinfunction "P$5_P$5") (pintype "power_in"))
      (node (ref "X5") (pin "2") (pinfunction "2_2") (pintype "bidirectional"))
    )
    (net (code "33") (name "Net-(D4-PadA)") (class "Default")
      (node (ref "D4") (pin "A") (pinfunction "A_A") (pintype "passive"))
      (node (ref "JP1") (pin "1") (pinfunction "1_1") (pintype "passive"))
      (node (ref "U7") (pin "P$1") (pinfunction "P$1_P$1") (pintype "input"))
    )
    (net (code "34") (name "Net-(D5-PadA)") (class "Default")
      (node (ref "D5") (pin "A") (pinfunction "A_A") (pintype "passive"))
      (node (ref "JP3") (pin "1") (pinfunction "1_1") (pintype "passive"))
      (node (ref "U10") (pin "P$1") (pinfunction "P$1_P$1") (pintype "input"))
    )
    (net (code "35") (name "Net-(JP2-Pad1)") (class "Default")
      (node (ref "JP2") (pin "1") (pinfunction "1_1") (pintype "passive"))
      (node (ref "JP3") (pin "2") (pinfunction "2_2") (pintype "passive"))
      (node (ref "X7") (pin "1") (pinfunction "1_1") (pintype "bidirectional"))
    )
    (net (code "36") (name "Net-(L1-1)") (class "Default")
      (node (ref "L1") (pin "P$1") (pinfunction "1_P$1") (pintype "passive"))
      (node (ref "U6") (pin "3") (pinfunction "P$3_3") (pintype "passive"))
    )
    (net (code "37") (name "Net-(L1-2)") (class "Default")
      (node (ref "D2") (pin "A") (pinfunction "A_A") (pintype "passive"))
      (node (ref "L1") (pin "P$2") (pinfunction "2_P$2") (pintype "passive"))
      (node (ref "U6") (pin "1") (pinfunction "P$1_1") (pintype "power_in"))
      (node (ref "U6") (pin "2") (pinfunction "P$2_2") (pintype "power_in"))
    )
    (net (code "38") (name "Net-(L2-1)") (class "Default")
      (node (ref "C22") (pin "1") (pinfunction "1_1") (pintype "passive"))
      (node (ref "D3") (pin "C") (pinfunction "C_C") (pintype "passive"))
      (node (ref "L2") (pin "P$1") (pinfunction "1_P$1") (pintype "passive"))
      (node (ref "U8") (pin "12") (pinfunction "P$12_12") (pintype "output"))
    )
    (net (code "39") (name "Net-(R5-2)") (class "Default")
      (node (ref "R5") (pin "P$2") (pinfunction "2_P$2") (pintype "passive"))
      (node (ref "X2") (pin "1") (pinfunction "1_1") (pintype "bidirectional"))
    )
    (net (code "40") (name "Net-(TR1-D)") (class "Default")
      (node (ref "R10") (pin "1") (pinfunction "1_1") (pintype "passive"))
      (node (ref "TR1") (pin "3") (pinfunction "D_3") (pintype "bidirectional"))
      (node (ref "U1") (pin "3") (pinfunction "P$3_3") (pintype "input"))
    )
    (net (code "41") (name "Net-(TR1-G)") (class "Default")
      (node (ref "R3") (pin "2") (pinfunction "2_2") (pintype "passive"))
      (node (ref "TR1") (pin "1") (pinfunction "G_1") (pintype "bidirectional"))
    )
    (net (code "42") (name "Net-(TR2-D)") (class "Default")
      (node (ref "R9") (pin "1") (pinfunction "1_1") (pintype "passive"))
      (node (ref "TR2") (pin "3") (pinfunction "D_3") (pintype "bidirectional"))
      (node (ref "U2") (pin "3") (pinfunction "P$3_3") (pintype "input"))
    )
    (net (code "43") (name "Net-(TR2-G)") (class "Default")
      (node (ref "R8") (pin "2") (pinfunction "2_2") (pintype "passive"))
      (node (ref "TR2") (pin "1") (pinfunction "G_1") (pintype "bidirectional"))
    )
    (net (code "44") (name "Net-(TR3-D)") (class "Default")
      (node (ref "R13") (pin "1") (pinfunction "1_1") (pintype "passive"))
      (node (ref "TR3") (pin "3") (pinfunction "D_3") (pintype "bidirectional"))
      (node (ref "U3") (pin "P$3") (pinfunction "P$3_P$3") (pintype "input"))
    )
    (net (code "45") (name "Net-(TR3-G)") (class "Default")
      (node (ref "R12") (pin "2") (pinfunction "2_2") (pintype "passive"))
      (node (ref "TR3") (pin "1") (pinfunction "G_1") (pintype "bidirectional"))
    )
    (net (code "46") (name "Net-(U1-P$5)") (class "Default")
      (node (ref "R4") (pin "2") (pinfunction "2_2") (pintype "passive"))
      (node (ref "U1") (pin "5") (pinfunction "P$5_5") (pintype "passive"))
    )
    (net (code "47") (name "Net-(U2-P$5)") (class "Default")
      (node (ref "R7") (pin "2") (pinfunction "2_2") (pintype "passive"))
      (node (ref "U2") (pin "5") (pinfunction "P$5_5") (pintype "passive"))
    )
    (net (code "48") (name "Net-(U4-P$3)") (class "Default")
      (node (ref "R18") (pin "2") (pinfunction "2_2") (pintype "passive"))
      (node (ref "U4") (pin "3") (pinfunction "P$3_3") (pintype "input"))
    )
    (net (code "49") (name "Net-(U4-P$5)") (class "Default")
      (node (ref "R16") (pin "1") (pinfunction "1_1") (pintype "passive"))
      (node (ref "R20") (pin "2") (pinfunction "2_2") (pintype "passive"))
      (node (ref "U4") (pin "5") (pinfunction "P$5_5") (pintype "input"))
    )
    (net (code "50") (name "Net-(U4-P$6)") (class "Default")
      (node (ref "R22") (pin "2") (pinfunction "2_2") (pintype "passive"))
      (node (ref "U4") (pin "6") (pinfunction "P$6_6") (pintype "input"))
      (node (ref "U5") (pin "4") (pinfunction "P$4_4") (pintype "bidirectional"))
    )
    (net (code "51") (name "Net-(U4-P$7)") (class "Default")
      (node (ref "R21") (pin "2") (pinfunction "2_2") (pintype "passive"))
      (node (ref "U4") (pin "7") (pinfunction "P$7_7") (pintype "input"))
    )
    (net (code "52") (name "Net-(U4-P$9)") (class "Default")
      (node (ref "R17") (pin "2") (pinfunction "2_2") (pintype "passive"))
      (node (ref "R21") (pin "1") (pinfunction "1_1") (pintype "passive"))
      (node (ref "U4") (pin "9") (pinfunction "P$9_9") (pintype "input"))
    )
    (net (code "53") (name "Net-(U6-P$6)") (class "Default")
      (node (ref "R24") (pin "2") (pinfunction "2_2") (pintype "passive"))
      (node (ref "U6") (pin "6") (pinfunction "P$6_6") (pintype "passive"))
    )
    (net (code "54") (name "Net-(U6-P$10)") (class "Default")
      (node (ref "C7") (pin "1") (pinfunction "1_1") (pintype "passive"))
      (node (ref "U6") (pin "10") (pinfunction "P$10_10") (pintype "input"))
      (node (ref "U6") (pin "9") (pinfunction "P$9_9") (pintype "output"))
    )
    (net (code "55") (name "Net-(U6-P$11)") (class "Default")
      (node (ref "C19") (pin "2") (pinfunction "2_2") (pintype "passive"))
      (node (ref "R25") (pin "2") (pinfunction "2_2") (pintype "passive"))
      (node (ref "R27") (pin "1") (pinfunction "1_1") (pintype "passive"))
      (node (ref "U6") (pin "11") (pinfunction "P$11_11") (pintype "input"))
    )
    (net (code "56") (name "Net-(U6-P$12)") (class "Default")
      (node (ref "R31") (pin "2") (pinfunction "2_2") (pintype "passive"))
      (node (ref "U6") (pin "12") (pinfunction "P$12_12") (pintype "input"))
    )
    (net (code "57") (name "Net-(U6-P$13)") (class "Default")
      (node (ref "C15") (pin "2") (pinfunction "2_2") (pintype "passive"))
      (node (ref "U6") (pin "13") (pinfunction "P$13_13") (pintype "input"))
    )
    (net (code "58") (name "Net-(U8-P$2)") (class "Default")
      (node (ref "R29") (pin "2") (pinfunction "2_2") (pintype "passive"))
      (node (ref "R34") (pin "1") (pinfunction "1_1") (pintype "passive"))
      (node (ref "U8") (pin "2") (pinfunction "P$2_2") (pintype "input"))
    )
    (net (code "59") (name "Net-(U8-P$3)") (class "Default")
      (node (ref "R28") (pin "2") (pinfunction "2_2") (pintype "passive"))
      (node (ref "R33") (pin "1") (pinfunction "1_1") (pintype "passive"))
      (node (ref "U8") (pin "3") (pinfunction "P$3_3") (pintype "input"))
    )
    (net (code "60") (name "Net-(U8-P$6)") (class "Default")
      (node (ref "C10") (pin "1") (pinfunction "1_1") (pintype "passive"))
      (node (ref "U8") (pin "6") (pinfunction "P$6_6") (pintype "input"))
    )
    (net (code "61") (name "Net-(U8-P$7)") (class "Default")
      (node (ref "R30") (pin "2") (pinfunction "2_2") (pintype "passive"))
      (node (ref "R32") (pin "1") (pinfunction "1_1") (pintype "passive"))
      (node (ref "U8") (pin "7") (pinfunction "P$7_7") (pintype "input"))
    )
    (net (code "62") (name "Net-(U8-P$11)") (class "Default")
      (node (ref "C22") (pin "2") (pinfunction "2_2") (pintype "passive"))
      (node (ref "D1") (pin "C") (pinfunction "C_C") (pintype "passive"))
      (node (ref "U8") (pin "11") (pinfunction "P$11_11") (pintype "input"))
    )
    (net (code "63") (name "Net-(X5-Pad1)") (class "Default")
      (node (ref "X5") (pin "1") (pinfunction "1_1") (pintype "bidirectional"))
      (node (ref "X6") (pin "NC") (pinfunction "NC_NC") (pintype "bidirectional"))
    )
    (net (code "64") (name "OBC_-FAULT") (class "Default")
      (node (ref "X1") (pin "34") (pinfunction "34_34") (pintype "bidirectional"))
    )
    (net (code "65") (name "OBC_OFF") (class "Default")
      (node (ref "X1") (pin "26") (pinfunction "26_26") (pintype "bidirectional"))
    )
    (net (code "66") (name "PANELTEMP_SCL") (class "Default")
      (node (ref "X1") (pin "29") (pinfunction "29_29") (pintype "bidirectional"))
    )
    (net (code "67") (name "PANELTEMP_SDA") (class "Default")
      (node (ref "X1") (pin "31") (pinfunction "31_31") (pintype "bidirectional"))
    )
    (net (code "68") (name "SCCHG_EN") (class "Default")
      (node (ref "R23") (pin "1") (pinfunction "1_1") (pintype "passive"))
      (node (ref "U5") (pin "3") (pinfunction "P$3_3") (pintype "bidirectional"))
      (node (ref "X1") (pin "21") (pinfunction "21_21") (pintype "bidirectional"))
    )
    (net (code "69") (name "SCOUT_-PG") (class "Default")
      (node (ref "X1") (pin "50") (pinfunction "50_50") (pintype "bidirectional"))
    )
    (net (code "70") (name "SCOUT_EN") (class "Default")
      (node (ref "R11") (pin "2") (pinfunction "2_2") (pintype "passive"))
      (node (ref "R12") (pin "1") (pinfunction "1_1") (pintype "passive"))
      (node (ref "X1") (pin "22") (pinfunction "22_22") (pintype "bidirectional"))
    )
    (net (code "71") (name "SC_-ON") (class "Default")
      (node (ref "R15") (pin "1") (pinfunction "1_1") (pintype "passive"))
      (node (ref "U3") (pin "P$4") (pinfunction "P$4_P$4") (pintype "output"))
      (node (ref "X1") (pin "40") (pinfunction "40_40") (pintype "bidirectional"))
    )
    (net (code "72") (name "SC_-PFO") (class "Default")
      (node (ref "R19") (pin "2") (pinfunction "2_2") (pintype "passive"))
      (node (ref "U4") (pin "8") (pinfunction "P$8_8") (pintype "output"))
      (node (ref "X1") (pin "48") (pinfunction "48_48") (pintype "bidirectional"))
    )
    (net (code "73") (name "SENSE") (class "Default")
      (node (ref "L2") (pin "P$2") (pinfunction "2_P$2") (pintype "passive"))
      (node (ref "R36") (pin "P$1") (pinfunction "1_P$1") (pintype "passive"))
      (node (ref "U8") (pin "10") (pinfunction "P$10_10") (pintype "input"))
    )
    (net (code "74") (name "SOLAR_-ON") (class "Default")
      (node (ref "R40") (pin "1") (pinfunction "1_1") (pintype "passive"))
      (node (ref "U10") (pin "P$4") (pinfunction "P$4_P$4") (pintype "output"))
      (node (ref "X1") (pin "36") (pinfunction "36_36") (pintype "bidirectional"))
    )
    (net (code "75") (name "SOLAR_CS1") (class "Default")
      (node (ref "X1") (pin "15") (pinfunction "15_15") (pintype "bidirectional"))
    )
    (net (code "76") (name "SOLAR_CS2") (class "Default")
      (node (ref "X1") (pin "14") (pinfunction "14_14") (pintype "bidirectional"))
    )
    (net (code "77") (name "SOLAR_CS3") (class "Default")
      (node (ref "X1") (pin "17") (pinfunction "17_17") (pintype "bidirectional"))
    )
    (net (code "78") (name "SOLAR_CS4") (class "Default")
      (node (ref "X1") (pin "16") (pinfunction "16_16") (pintype "bidirectional"))
    )
    (net (code "79") (name "SOLAR_CS5") (class "Default")
      (node (ref "X1") (pin "18") (pinfunction "18_18") (pintype "bidirectional"))
    )
    (net (code "80") (name "STRUT_GND") (class "Default")
      (node (ref "C1") (pin "1") (pinfunction "1_1") (pintype "passive"))
      (node (ref "H4") (pin "B3,2") (pinfunction "MOUNT_B3,2") (pintype "passive"))
      (node (ref "R1") (pin "P$2") (pinfunction "2_P$2") (pintype "passive"))
    )
    (net (code "81") (name "SUPERCAP_TEMP") (class "Default")
      (node (ref "X1") (pin "49") (pinfunction "49_49") (pintype "bidirectional"))
    )
    (net (code "82") (name "VBAT") (class "Default")
      (node (ref "C11") (pin "1") (pinfunction "1_1") (pintype "passive"))
      (node (ref "C16") (pin "P$1") (pinfunction "1_P$1") (pintype "passive"))
      (node (ref "C17") (pin "P$1") (pinfunction "1_P$1") (pintype "passive"))
      (node (ref "D1") (pin "A") (pinfunction "A_A") (pintype "passive"))
      (node (ref "JP1") (pin "2") (pinfunction "2_2") (pintype "passive"))
      (node (ref "R10") (pin "2") (pinfunction "2_2") (pintype "passive"))
      (node (ref "R13") (pin "2") (pinfunction "2_2") (pintype "passive"))
      (node (ref "R32") (pin "2") (pinfunction "2_2") (pintype "passive"))
      (node (ref "R36") (pin "P$2") (pinfunction "2_P$2") (pintype "passive"))
      (node (ref "R9") (pin "2") (pinfunction "2_2") (pintype "passive"))
      (node (ref "U1") (pin "1") (pinfunction "P$1_1") (pintype "input"))
      (node (ref "U1") (pin "2") (pinfunction "P$2_2") (pintype "input"))
      (node (ref "U2") (pin "1") (pinfunction "P$1_1") (pintype "input"))
      (node (ref "U2") (pin "2") (pinfunction "P$2_2") (pintype "input"))
      (node (ref "U3") (pin "P$1") (pinfunction "P$1_P$1") (pintype "input"))
      (node (ref "U8") (pin "9") (pinfunction "P$9_9") (pintype "input"))
      (node (ref "X1") (pin "11") (pinfunction "11_11") (pintype "bidirectional"))
      (node (ref "X1") (pin "12") (pinfunction "12_12") (pintype "bidirectional"))
      (node (ref "X4") (pin "1") (pinfunction "1_1") (pintype "bidirectional"))
    )
    (net (code "83") (name "VBUS") (class "Default")
      (node (ref "R15") (pin "2") (pinfunction "2_2") (pintype "passive"))
      (node (ref "R19") (pin "1") (pinfunction "1_1") (pintype "passive"))
      (node (ref "R35") (pin "P$2") (pinfunction "2_P$2") (pintype "passive"))
      (node (ref "R37") (pin "2") (pinfunction "2_2") (pintype "passive"))
      (node (ref "R38") (pin "2") (pinfunction "2_2") (pintype "passive"))
      (node (ref "R39") (pin "2") (pinfunction "2_2") (pintype "passive"))
      (node (ref "R40") (pin "2") (pinfunction "2_2") (pintype "passive"))
      (node (ref "U9") (pin "5") (pinfunction "P$5_5") (pintype "input"))
      (node (ref "X1") (pin "10") (pinfunction "10_10") (pintype "bidirectional"))
      (node (ref "X1") (pin "7") (pinfunction "7_7") (pintype "bidirectional"))
      (node (ref "X1") (pin "8") (pinfunction "8_8") (pintype "bidirectional"))
      (node (ref "X1") (pin "9") (pinfunction "9_9") (pintype "bidirectional"))
    )
    (net (code "84") (name "VMID") (class "Default")
      (node (ref "U4") (pin "10") (pinfunction "P$10_10") (pintype "power_in"))
      (node (ref "X3") (pin "2") (pinfunction "2_2") (pintype "bidirectional"))
    )
    (net (code "85") (name "VSC_IN") (class "Default")
      (node (ref "C4") (pin "P$1") (pinfunction "1_P$1") (pintype "passive"))
      (node (ref "R17") (pin "1") (pinfunction "1_1") (pintype "passive"))
      (node (ref "U3") (pin "P$5") (pinfunction "P$5_P$5") (pintype "power_in"))
      (node (ref "U4") (pin "11") (pinfunction "P$11_11") (pintype "power_in"))
      (node (ref "U4") (pin "12") (pinfunction "P$12_12") (pintype "power_in"))
      (node (ref "U5") (pin "6") (pinfunction "P$6_6") (pintype "bidirectional"))
    )
    (net (code "86") (name "VSOLAR") (class "Default")
      (node (ref "X1") (pin "3") (pinfunction "3_3") (pintype "bidirectional"))
      (node (ref "X1") (pin "4") (pinfunction "4_4") (pintype "bidirectional"))
      (node (ref "X1") (pin "5") (pinfunction "5_5") (pintype "bidirectional"))
      (node (ref "X1") (pin "6") (pinfunction "6_6") (pintype "bidirectional"))
      (node (ref "X7") (pin "2") (pinfunction "2_2") (pintype "bidirectional"))
    )
    (net (code "87") (name "VSUPERCAP") (class "Default")
      (node (ref "C6") (pin "P$1") (pinfunction "1_P$1") (pintype "passive"))
      (node (ref "R14") (pin "P$2") (pinfunction "2_P$2") (pintype "passive"))
      (node (ref "R20") (pin "1") (pinfunction "1_1") (pintype "passive"))
      (node (ref "U4") (pin "1") (pinfunction "P$1_1") (pintype "power_in"))
      (node (ref "U4") (pin "2") (pinfunction "P$2_2") (pintype "power_in"))
      (node (ref "X1") (pin "13") (pinfunction "13_13") (pintype "bidirectional"))
      (node (ref "X3") (pin "1") (pinfunction "1_1") (pintype "bidirectional"))
    )
    (net (code "88") (name "unconnected-(H1-MOUNT-PadB3,2)") (class "Default")
      (node (ref "H1") (pin "B3,2") (pinfunction "MOUNT_B3,2") (pintype "passive"))
    )
    (net (code "89") (name "unconnected-(H2-MOUNT-PadB3,2)") (class "Default")
      (node (ref "H2") (pin "B3,2") (pinfunction "MOUNT_B3,2") (pintype "passive"))
    )
    (net (code "90") (name "unconnected-(H3-MOUNT-PadB3,2)") (class "Default")
      (node (ref "H3") (pin "B3,2") (pinfunction "MOUNT_B3,2") (pintype "passive"))
    )
    (net (code "91") (name "unconnected-(U8-P$8-Pad8)") (class "Default")
      (node (ref "U8") (pin "8") (pinfunction "P$8_8") (pintype "input"))
    )
    (net (code "92") (name "unconnected-(X6-PadNO)") (class "Default")
      (node (ref "X6") (pin "NO") (pinfunction "NO_NO") (pintype "bidirectional"))
    )
  )
)
